# v1_0.net
KiCad netlist of a schematic drawn in Altium Designer
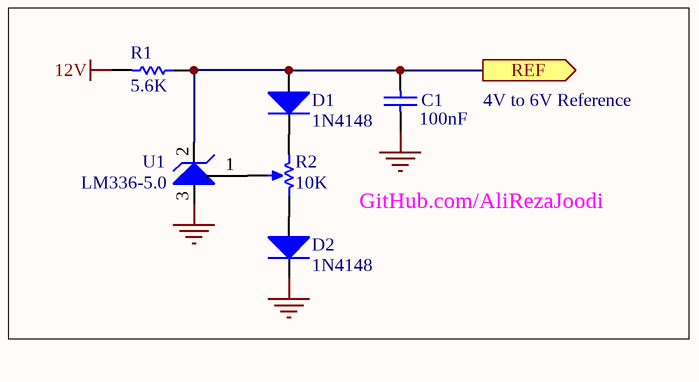
[diagram p0: v1.0.SchDoc]

(export (version "E")
  (design (tool "Eeschema 10.0.6"))
  (components
    (comp (ref "C1")
      (value "100nF")
      (footprint "CAPNTO2.54-3.05x1.78A")
      (description "Capacitor")
      (fields
        (field (name "MANUFACTURER") "Generic Components")
        (field (name "Comment") "Cap")
        (field (name "PUBLISHER") "Altium Limited")
      )
      (libsource (lib "Miscellaneous Devices") (part "Cap"))
    )
    (comp (ref "D1")
      (value "1N4148")
      (footprint "DIODE0.4_Glass")
      (description "Default Diode")
      (fields (field (name "MANUFACTURER") "Generic Components") (field (name "PUBLISHER") "Altium Limited"))
      (libsource (lib "Miscellaneous Devices") (part "Diode"))
    )
    (comp (ref "D2")
      (value "1N4148")
      (footprint "DIODE0.4_Glass")
      (description "Default Diode")
      (fields (field (name "MANUFACTURER") "Generic Components") (field (name "PUBLISHER") "Altium Limited"))
      (libsource (lib "Miscellaneous Devices") (part "Diode"))
    )
    (comp (ref "R1")
      (value "5.6K")
      (footprint "AXIAL-0.4")
      (description "Resistor")
      (fields (field (name "Comment") "Res1") (field (name "PUBLISHER") "Altium Limited"))
      (libsource (lib "Miscellaneous Devices") (part "Res1"))
    )
    (comp (ref "R2")
      (value "10K")
      (footprint "VR4_")
      (description "Potentiometer")
      (fields
        (field (name "MANUFACTURER") "Generic Components")
        (field (name "Comment") "POT")
        (field (name "PUBLISHER") "Altium Limited")
      )
      (libsource (lib "my Libraries") (part "RPot1"))
    )
    (comp (ref "U1")
      (value "LM336-5.0")
      (footprint "TO92C")
      (description "Programmable Shunt Regulator")
      (libsource (lib "my Libraries") (part "LM336"))
    )
  )
  (nets
    (net (code "1") (name "/REF") (class "Default")
      (node (ref "C1") (pin "1") (pinfunction "1_1") (pintype "passive"))
      (node (ref "D1") (pin "1") (pinfunction "A_1") (pintype "passive"))
      (node (ref "R1") (pin "1") (pinfunction "1_1") (pintype "passive"))
      (node (ref "U1") (pin "2") (pinfunction "+_2") (pintype "passive"))
    )
    (net (code "2") (name "12V") (class "Default")
      (node (ref "R1") (pin "2") (pinfunction "2_2") (pintype "passive"))
    )
    (net (code "3") (name "GND") (class "Default")
      (node (ref "C1") (pin "2") (pinfunction "2_2") (pintype "passive"))
      (node (ref "D2") (pin "2") (pinfunction "K_2") (pintype "passive"))
      (node (ref "U1") (pin "3") (pinfunction "-_3") (pintype "passive"))
    )
    (net (code "4") (name "Net-(D1-K)") (class "Default")
      (node (ref "D1") (pin "2") (pinfunction "K_2") (pintype "passive"))
      (node (ref "R2") (pin "2") (pinfunction "BOT_2") (pintype "passive"))
    )
    (net (code "5") (name "Net-(D2-A)") (class "Default")
      (node (ref "D2") (pin "1") (pinfunction "A_1") (pintype "passive"))
      (node (ref "R2") (pin "1") (pinfunction "TOP_1") (pintype "passive"))
    )
    (net (code "6") (name "Net-(R2-TAP)") (class "Default")
      (node (ref "R2") (pin "3") (pinfunction "TAP_3") (pintype "passive"))
      (node (ref "U1") (pin "1") (pinfunction "Adj_1") (pintype "passive"))
    )
  )
)
